# bbb_d300_cape.net
KiCad netlist of a schematic drawn in EAGLE
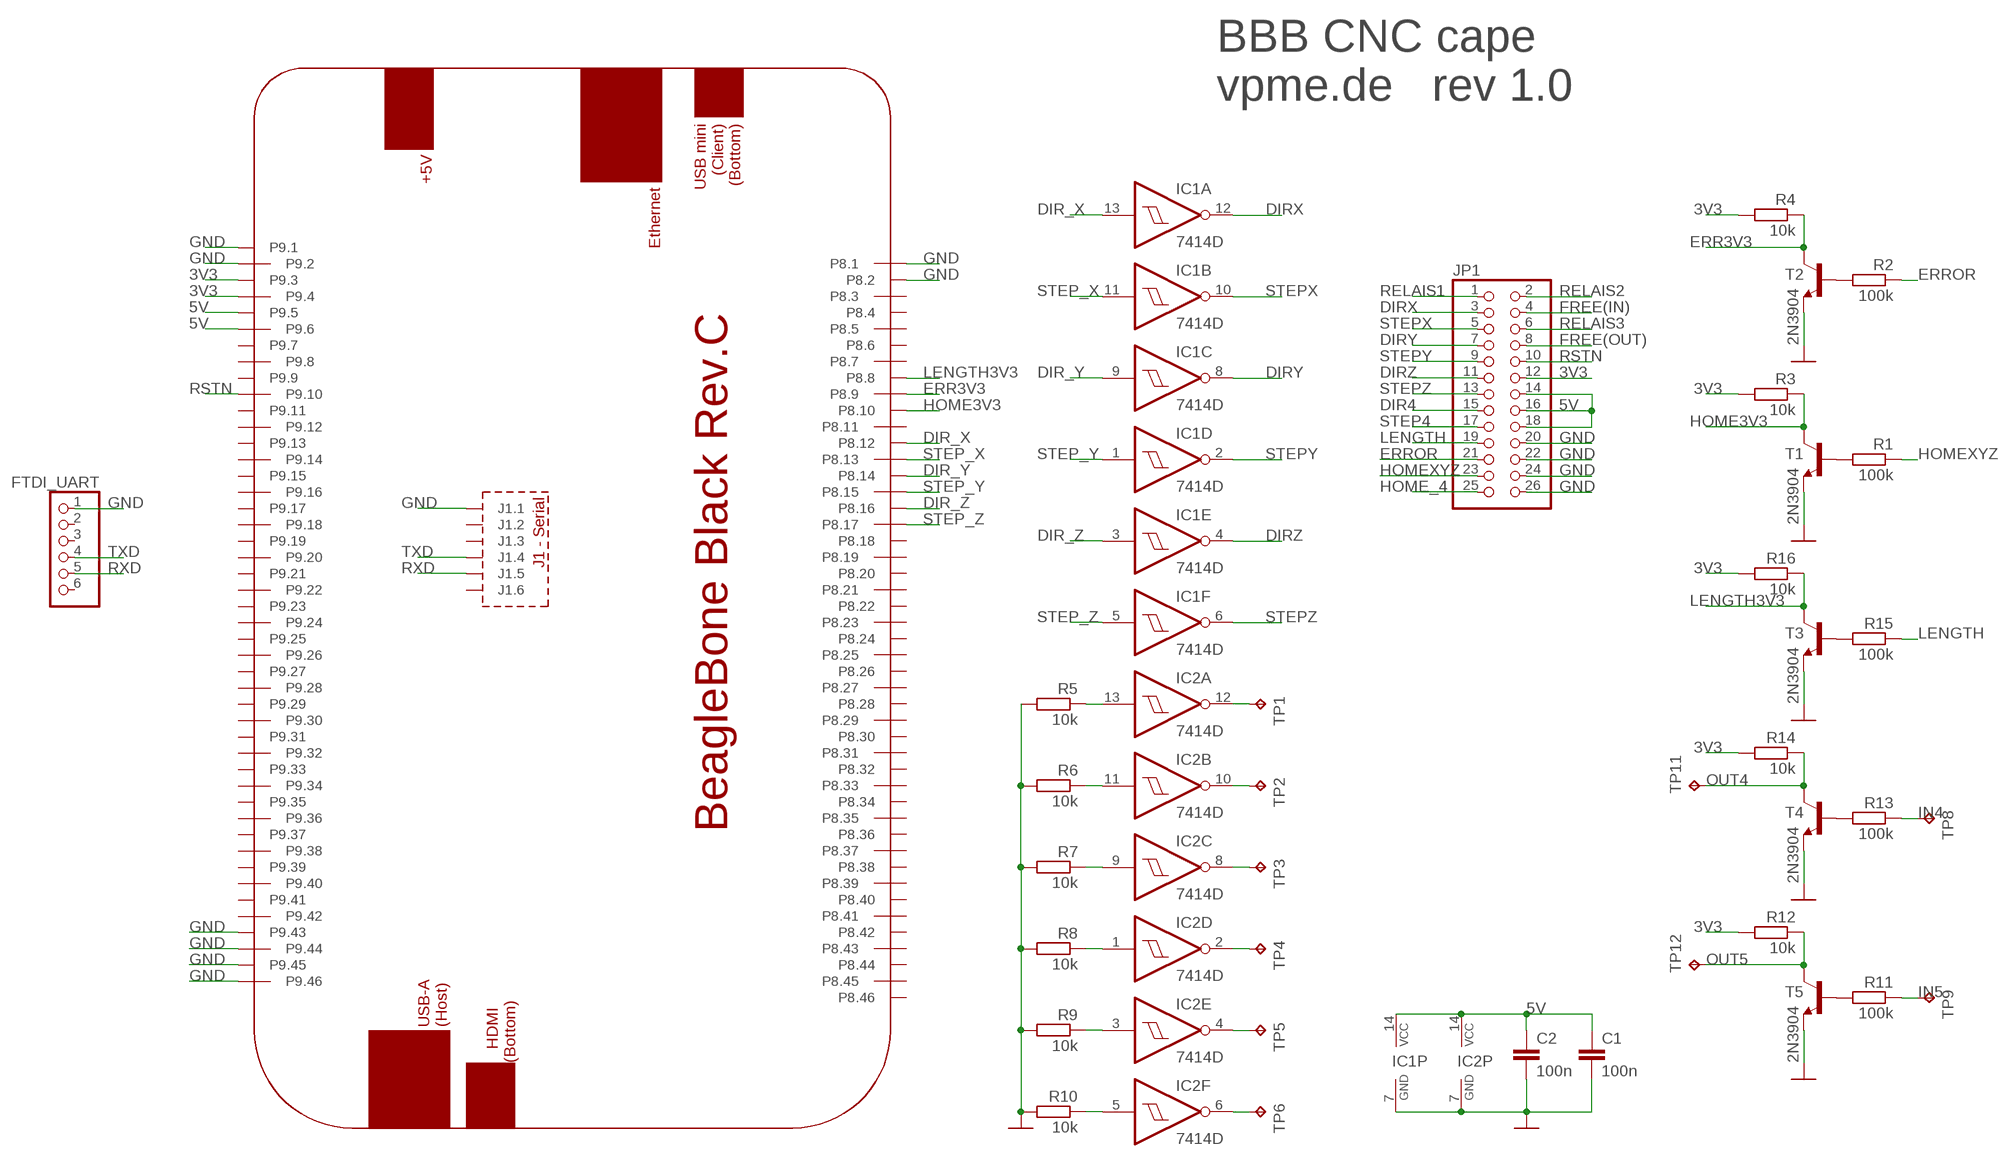
[diagram p0: schematic, sheet 1]

(export (version "E")
  (design (tool "Eeschema 10.0.6"))
  (components
    (comp (ref "C1")
      (value "100n")
      (footprint "eagle-import:C0603")
      (libsource (lib "eagle-import") (part "C-EUC0603"))
    )
    (comp (ref "C2")
      (value "100n")
      (footprint "eagle-import:C0603")
      (libsource (lib "eagle-import") (part "C-EUC0603"))
    )
    (comp (ref "FTDI_UART")
      (value "PINHD-1X6/90")
      (footprint "eagle-import:1X06_90")
      (libsource (lib "eagle-import") (part "PINHD-1X6/90"))
    )
    (comp (ref "IC1")
      (value "7414D")
      (footprint "eagle-import:SO14")
      (libsource (lib "eagle-import") (part "7414D"))
    )
    (comp (ref "IC2")
      (value "7414D")
      (footprint "eagle-import:SO14")
      (libsource (lib "eagle-import") (part "7414D"))
    )
    (comp (ref "JP1")
      (value "PINHD-2X13/90")
      (footprint "eagle-import:2X13_90")
      (libsource (lib "eagle-import") (part "PINHD-2X13/90"))
    )
    (comp (ref "PCB2")
      (value "BEAGLEBONE_BLACK_CAPE")
      (footprint "eagle-import:BEAGLEBONE_BLACK_CAPE")
      (libsource (lib "eagle-import") (part "BEAGLEBONE_BLACK_CAPE"))
    )
    (comp (ref "R1")
      (value "100k")
      (footprint "eagle-import:R0603")
      (libsource (lib "eagle-import") (part "R-EU_R0603"))
    )
    (comp (ref "R2")
      (value "100k")
      (footprint "eagle-import:R0603")
      (libsource (lib "eagle-import") (part "R-EU_R0603"))
    )
    (comp (ref "R3")
      (value "10k")
      (footprint "eagle-import:R0603")
      (libsource (lib "eagle-import") (part "R-EU_R0603"))
    )
    (comp (ref "R4")
      (value "10k")
      (footprint "eagle-import:R0603")
      (libsource (lib "eagle-import") (part "R-EU_R0603"))
    )
    (comp (ref "R5")
      (value "10k")
      (footprint "eagle-import:R0603")
      (libsource (lib "eagle-import") (part "R-EU_R0603"))
    )
    (comp (ref "R6")
      (value "10k")
      (footprint "eagle-import:R0603")
      (libsource (lib "eagle-import") (part "R-EU_R0603"))
    )
    (comp (ref "R7")
      (value "10k")
      (footprint "eagle-import:R0603")
      (libsource (lib "eagle-import") (part "R-EU_R0603"))
    )
    (comp (ref "R8")
      (value "10k")
      (footprint "eagle-import:R0603")
      (libsource (lib "eagle-import") (part "R-EU_R0603"))
    )
    (comp (ref "R9")
      (value "10k")
      (footprint "eagle-import:R0603")
      (libsource (lib "eagle-import") (part "R-EU_R0603"))
    )
    (comp (ref "R10")
      (value "10k")
      (footprint "eagle-import:R0603")
      (libsource (lib "eagle-import") (part "R-EU_R0603"))
    )
    (comp (ref "R11")
      (value "100k")
      (footprint "eagle-import:R0603")
      (libsource (lib "eagle-import") (part "R-EU_R0603"))
    )
    (comp (ref "R12")
      (value "10k")
      (footprint "eagle-import:R0603")
      (libsource (lib "eagle-import") (part "R-EU_R0603"))
    )
    (comp (ref "R13")
      (value "100k")
      (footprint "eagle-import:R0603")
      (libsource (lib "eagle-import") (part "R-EU_R0603"))
    )
    (comp (ref "R14")
      (value "10k")
      (footprint "eagle-import:R0603")
      (libsource (lib "eagle-import") (part "R-EU_R0603"))
    )
    (comp (ref "R15")
      (value "100k")
      (footprint "eagle-import:R0603")
      (libsource (lib "eagle-import") (part "R-EU_R0603"))
    )
    (comp (ref "R16")
      (value "10k")
      (footprint "eagle-import:R0603")
      (libsource (lib "eagle-import") (part "R-EU_R0603"))
    )
    (comp (ref "T1")
      (value "2N3904")
      (footprint "eagle-import:SOT23-BEC")
      (libsource (lib "eagle-import") (part "-NPN-SOT23-BECMMBT2222ALT1"))
    )
    (comp (ref "T2")
      (value "2N3904")
      (footprint "eagle-import:SOT23-BEC")
      (libsource (lib "eagle-import") (part "-NPN-SOT23-BECMMBT2222ALT1"))
    )
    (comp (ref "T3")
      (value "2N3904")
      (footprint "eagle-import:SOT23-BEC")
      (libsource (lib "eagle-import") (part "-NPN-SOT23-BECMMBT2222ALT1"))
    )
    (comp (ref "T4")
      (value "2N3904")
      (footprint "eagle-import:SOT23-BEC")
      (libsource (lib "eagle-import") (part "-NPN-SOT23-BECMMBT2222ALT1"))
    )
    (comp (ref "T5")
      (value "2N3904")
      (footprint "eagle-import:SOT23-BEC")
      (libsource (lib "eagle-import") (part "-NPN-SOT23-BECMMBT2222ALT1"))
    )
    (comp (ref "TP1")
      (value "TPTP12R")
      (footprint "eagle-import:TP12R")
      (libsource (lib "eagle-import") (part "TPTP12R"))
    )
    (comp (ref "TP2")
      (value "TPTP12R")
      (footprint "eagle-import:TP12R")
      (libsource (lib "eagle-import") (part "TPTP12R"))
    )
    (comp (ref "TP3")
      (value "TPTP12R")
      (footprint "eagle-import:TP12R")
      (libsource (lib "eagle-import") (part "TPTP12R"))
    )
    (comp (ref "TP4")
      (value "TPTP12R")
      (footprint "eagle-import:TP12R")
      (libsource (lib "eagle-import") (part "TPTP12R"))
    )
    (comp (ref "TP5")
      (value "TPTP12R")
      (footprint "eagle-import:TP12R")
      (libsource (lib "eagle-import") (part "TPTP12R"))
    )
    (comp (ref "TP6")
      (value "TPTP12R")
      (footprint "eagle-import:TP12R")
      (libsource (lib "eagle-import") (part "TPTP12R"))
    )
    (comp (ref "TP8")
      (value "TPTP12R")
      (footprint "eagle-import:TP12R")
      (libsource (lib "eagle-import") (part "TPTP12R"))
    )
    (comp (ref "TP9")
      (value "TPTP12R")
      (footprint "eagle-import:TP12R")
      (libsource (lib "eagle-import") (part "TPTP12R"))
    )
    (comp (ref "TP11")
      (value "TPTP12R")
      (footprint "eagle-import:TP12R")
      (libsource (lib "eagle-import") (part "TPTP12R"))
    )
    (comp (ref "TP12")
      (value "TPTP12R")
      (footprint "eagle-import:TP12R")
      (libsource (lib "eagle-import") (part "TPTP12R"))
    )
  )
  (nets
    (net (code "1") (name "/3V3") (class "Default")
      (node (ref "JP1") (pin "12") (pinfunction "12_12") (pintype "passive"))
      (node (ref "PCB2") (pin "P9.3") (pinfunction "P9.3_P9.3") (pintype "bidirectional"))
      (node (ref "PCB2") (pin "P9.4") (pinfunction "P9.4_P9.4") (pintype "bidirectional"))
      (node (ref "R12") (pin "2") (pinfunction "2_2") (pintype "passive"))
      (node (ref "R14") (pin "2") (pinfunction "2_2") (pintype "passive"))
      (node (ref "R16") (pin "2") (pinfunction "2_2") (pintype "passive"))
      (node (ref "R3") (pin "2") (pinfunction "2_2") (pintype "passive"))
      (node (ref "R4") (pin "2") (pinfunction "2_2") (pintype "passive"))
    )
    (net (code "2") (name "/5V") (class "Default")
      (node (ref "C1") (pin "1") (pinfunction "1_1") (pintype "passive"))
      (node (ref "C2") (pin "1") (pinfunction "1_1") (pintype "passive"))
      (node (ref "IC1") (pin "14") (pinfunction "VCC_14") (pintype "power_in"))
      (node (ref "IC2") (pin "14") (pinfunction "VCC_14") (pintype "power_in"))
      (node (ref "JP1") (pin "14") (pinfunction "14_14") (pintype "passive"))
      (node (ref "JP1") (pin "16") (pinfunction "16_16") (pintype "passive"))
      (node (ref "JP1") (pin "18") (pinfunction "18_18") (pintype "passive"))
      (node (ref "PCB2") (pin "P9.5") (pinfunction "P9.5_P9.5") (pintype "bidirectional"))
      (node (ref "PCB2") (pin "P9.6") (pinfunction "P9.6_P9.6") (pintype "bidirectional"))
    )
    (net (code "3") (name "/DIR4") (class "Default")
      (node (ref "JP1") (pin "15") (pinfunction "15_15") (pintype "passive"))
    )
    (net (code "4") (name "/DIRX") (class "Default")
      (node (ref "IC1") (pin "12") (pinfunction "O_12") (pintype "output"))
      (node (ref "JP1") (pin "3") (pinfunction "3_3") (pintype "passive"))
    )
    (net (code "5") (name "/DIRY") (class "Default")
      (node (ref "IC1") (pin "8") (pinfunction "O_8") (pintype "output"))
      (node (ref "JP1") (pin "7") (pinfunction "7_7") (pintype "passive"))
    )
    (net (code "6") (name "/DIRZ") (class "Default")
      (node (ref "IC1") (pin "4") (pinfunction "O_4") (pintype "output"))
      (node (ref "JP1") (pin "11") (pinfunction "11_11") (pintype "passive"))
    )
    (net (code "7") (name "/DIR_X") (class "Default")
      (node (ref "IC1") (pin "13") (pinfunction "I_13") (pintype "input"))
      (node (ref "PCB2") (pin "P8.12") (pinfunction "P8.12_P8.12") (pintype "bidirectional"))
    )
    (net (code "8") (name "/DIR_Y") (class "Default")
      (node (ref "IC1") (pin "9") (pinfunction "I_9") (pintype "input"))
      (node (ref "PCB2") (pin "P8.14") (pinfunction "P8.14_P8.14") (pintype "bidirectional"))
    )
    (net (code "9") (name "/DIR_Z") (class "Default")
      (node (ref "IC1") (pin "3") (pinfunction "I_3") (pintype "input"))
      (node (ref "PCB2") (pin "P8.16") (pinfunction "P8.16_P8.16") (pintype "bidirectional"))
    )
    (net (code "10") (name "/ERR3V3") (class "Default")
      (node (ref "PCB2") (pin "P8.9") (pinfunction "P8.9_P8.9") (pintype "bidirectional"))
      (node (ref "R4") (pin "1") (pinfunction "1_1") (pintype "passive"))
      (node (ref "T2") (pin "C") (pinfunction "C_C") (pintype "passive"))
    )
    (net (code "11") (name "/ERROR") (class "Default")
      (node (ref "JP1") (pin "21") (pinfunction "21_21") (pintype "passive"))
      (node (ref "R2") (pin "1") (pinfunction "1_1") (pintype "passive"))
    )
    (net (code "12") (name "/FREE(IN)") (class "Default")
      (node (ref "JP1") (pin "4") (pinfunction "4_4") (pintype "passive"))
    )
    (net (code "13") (name "/FREE(OUT)") (class "Default")
      (node (ref "JP1") (pin "8") (pinfunction "8_8") (pintype "passive"))
    )
    (net (code "14") (name "/HOME3V3") (class "Default")
      (node (ref "PCB2") (pin "P8.10") (pinfunction "P8.10_P8.10") (pintype "bidirectional"))
      (node (ref "R3") (pin "1") (pinfunction "1_1") (pintype "passive"))
      (node (ref "T1") (pin "C") (pinfunction "C_C") (pintype "passive"))
    )
    (net (code "15") (name "/HOMEXYZ") (class "Default")
      (node (ref "JP1") (pin "23") (pinfunction "23_23") (pintype "passive"))
      (node (ref "R1") (pin "1") (pinfunction "1_1") (pintype "passive"))
    )
    (net (code "16") (name "/HOME_4") (class "Default")
      (node (ref "JP1") (pin "25") (pinfunction "25_25") (pintype "passive"))
    )
    (net (code "17") (name "/IN4") (class "Default")
      (node (ref "R13") (pin "1") (pinfunction "1_1") (pintype "passive"))
      (node (ref "TP8") (pin "TP") (pinfunction "TP_TP") (pintype "input"))
    )
    (net (code "18") (name "/IN5") (class "Default")
      (node (ref "R11") (pin "1") (pinfunction "1_1") (pintype "passive"))
      (node (ref "TP9") (pin "TP") (pinfunction "TP_TP") (pintype "input"))
    )
    (net (code "19") (name "/LENGTH") (class "Default")
      (node (ref "JP1") (pin "19") (pinfunction "19_19") (pintype "passive"))
      (node (ref "R15") (pin "1") (pinfunction "1_1") (pintype "passive"))
    )
    (net (code "20") (name "/LENGTH3V3") (class "Default")
      (node (ref "PCB2") (pin "P8.8") (pinfunction "P8.8_P8.8") (pintype "bidirectional"))
      (node (ref "R16") (pin "1") (pinfunction "1_1") (pintype "passive"))
      (node (ref "T3") (pin "C") (pinfunction "C_C") (pintype "passive"))
    )
    (net (code "21") (name "/OUT4") (class "Default")
      (node (ref "R14") (pin "1") (pinfunction "1_1") (pintype "passive"))
      (node (ref "T4") (pin "C") (pinfunction "C_C") (pintype "passive"))
      (node (ref "TP11") (pin "TP") (pinfunction "TP_TP") (pintype "input"))
    )
    (net (code "22") (name "/OUT5") (class "Default")
      (node (ref "R12") (pin "1") (pinfunction "1_1") (pintype "passive"))
      (node (ref "T5") (pin "C") (pinfunction "C_C") (pintype "passive"))
      (node (ref "TP12") (pin "TP") (pinfunction "TP_TP") (pintype "input"))
    )
    (net (code "23") (name "/RELAIS1") (class "Default")
      (node (ref "JP1") (pin "1") (pinfunction "1_1") (pintype "passive"))
    )
    (net (code "24") (name "/RELAIS2") (class "Default")
      (node (ref "JP1") (pin "2") (pinfunction "2_2") (pintype "passive"))
    )
    (net (code "25") (name "/RELAIS3") (class "Default")
      (node (ref "JP1") (pin "6") (pinfunction "6_6") (pintype "passive"))
    )
    (net (code "26") (name "/RSTN") (class "Default")
      (node (ref "JP1") (pin "10") (pinfunction "10_10") (pintype "passive"))
      (node (ref "PCB2") (pin "P9.10") (pinfunction "P9.10_P9.10") (pintype "bidirectional"))
    )
    (net (code "27") (name "/RXD") (class "Default")
      (node (ref "FTDI_UART") (pin "5") (pinfunction "5_5") (pintype "passive"))
      (node (ref "PCB2") (pin "J1.5") (pinfunction "J1.5_J1.5") (pintype "bidirectional"))
    )
    (net (code "28") (name "/STEP4") (class "Default")
      (node (ref "JP1") (pin "17") (pinfunction "17_17") (pintype "passive"))
    )
    (net (code "29") (name "/STEPX") (class "Default")
      (node (ref "IC1") (pin "10") (pinfunction "O_10") (pintype "output"))
      (node (ref "JP1") (pin "5") (pinfunction "5_5") (pintype "passive"))
    )
    (net (code "30") (name "/STEPY") (class "Default")
      (node (ref "IC1") (pin "2") (pinfunction "O_2") (pintype "output"))
      (node (ref "JP1") (pin "9") (pinfunction "9_9") (pintype "passive"))
    )
    (net (code "31") (name "/STEPZ") (class "Default")
      (node (ref "IC1") (pin "6") (pinfunction "O_6") (pintype "output"))
      (node (ref "JP1") (pin "13") (pinfunction "13_13") (pintype "passive"))
    )
    (net (code "32") (name "/STEP_X") (class "Default")
      (node (ref "IC1") (pin "11") (pinfunction "I_11") (pintype "input"))
      (node (ref "PCB2") (pin "P8.13") (pinfunction "P8.13_P8.13") (pintype "bidirectional"))
    )
    (net (code "33") (name "/STEP_Y") (class "Default")
      (node (ref "IC1") (pin "1") (pinfunction "I_1") (pintype "input"))
      (node (ref "PCB2") (pin "P8.15") (pinfunction "P8.15_P8.15") (pintype "bidirectional"))
    )
    (net (code "34") (name "/STEP_Z") (class "Default")
      (node (ref "IC1") (pin "5") (pinfunction "I_5") (pintype "input"))
      (node (ref "PCB2") (pin "P8.17") (pinfunction "P8.17_P8.17") (pintype "bidirectional"))
    )
    (net (code "35") (name "/TXD") (class "Default")
      (node (ref "FTDI_UART") (pin "4") (pinfunction "4_4") (pintype "passive"))
      (node (ref "PCB2") (pin "J1.4") (pinfunction "J1.4_J1.4") (pintype "bidirectional"))
    )
    (net (code "36") (name "GND") (class "Default")
      (node (ref "C1") (pin "2") (pinfunction "2_2") (pintype "passive"))
      (node (ref "C2") (pin "2") (pinfunction "2_2") (pintype "passive"))
      (node (ref "FTDI_UART") (pin "1") (pinfunction "1_1") (pintype "passive"))
      (node (ref "IC1") (pin "7") (pinfunction "GND_7") (pintype "power_in"))
      (node (ref "IC2") (pin "7") (pinfunction "GND_7") (pintype "power_in"))
      (node (ref "JP1") (pin "20") (pinfunction "20_20") (pintype "passive"))
      (node (ref "JP1") (pin "22") (pinfunction "22_22") (pintype "passive"))
      (node (ref "JP1") (pin "24") (pinfunction "24_24") (pintype "passive"))
      (node (ref "JP1") (pin "26") (pinfunction "26_26") (pintype "passive"))
      (node (ref "PCB2") (pin "J1.1") (pinfunction "J1.1_J1.1") (pintype "bidirectional"))
      (node (ref "PCB2") (pin "P8.1") (pinfunction "P8.1_P8.1") (pintype "bidirectional"))
      (node (ref "PCB2") (pin "P8.2") (pinfunction "P8.2_P8.2") (pintype "bidirectional"))
      (node (ref "PCB2") (pin "P9.1") (pinfunction "P9.1_P9.1") (pintype "bidirectional"))
      (node (ref "PCB2") (pin "P9.2") (pinfunction "P9.2_P9.2") (pintype "bidirectional"))
      (node (ref "PCB2") (pin "P9.43") (pinfunction "P9.43_P9.43") (pintype "bidirectional"))
      (node (ref "PCB2") (pin "P9.44") (pinfunction "P9.44_P9.44") (pintype "bidirectional"))
      (node (ref "PCB2") (pin "P9.45") (pinfunction "P9.45_P9.45") (pintype "bidirectional"))
      (node (ref "PCB2") (pin "P9.46") (pinfunction "P9.46_P9.46") (pintype "bidirectional"))
      (node (ref "R10") (pin "2") (pinfunction "2_2") (pintype "passive"))
      (node (ref "R5") (pin "2") (pinfunction "2_2") (pintype "passive"))
      (node (ref "R6") (pin "2") (pinfunction "2_2") (pintype "passive"))
      (node (ref "R7") (pin "2") (pinfunction "2_2") (pintype "passive"))
      (node (ref "R8") (pin "2") (pinfunction "2_2") (pintype "passive"))
      (node (ref "R9") (pin "2") (pinfunction "2_2") (pintype "passive"))
      (node (ref "T1") (pin "E") (pinfunction "E_E") (pintype "passive"))
      (node (ref "T2") (pin "E") (pinfunction "E_E") (pintype "passive"))
      (node (ref "T3") (pin "E") (pinfunction "E_E") (pintype "passive"))
      (node (ref "T4") (pin "E") (pinfunction "E_E") (pintype "passive"))
      (node (ref "T5") (pin "E") (pinfunction "E_E") (pintype "passive"))
    )
    (net (code "37") (name "Net-(IC2A-I)") (class "Default")
      (node (ref "IC2") (pin "13") (pinfunction "I_13") (pintype "input"))
      (node (ref "R5") (pin "1") (pinfunction "1_1") (pintype "passive"))
    )
    (net (code "38") (name "Net-(IC2A-O)") (class "Default")
      (node (ref "IC2") (pin "12") (pinfunction "O_12") (pintype "output"))
      (node (ref "TP1") (pin "TP") (pinfunction "TP_TP") (pintype "input"))
    )
    (net (code "39") (name "Net-(IC2B-I)") (class "Default")
      (node (ref "IC2") (pin "11") (pinfunction "I_11") (pintype "input"))
      (node (ref "R6") (pin "1") (pinfunction "1_1") (pintype "passive"))
    )
    (net (code "40") (name "Net-(IC2B-O)") (class "Default")
      (node (ref "IC2") (pin "10") (pinfunction "O_10") (pintype "output"))
      (node (ref "TP2") (pin "TP") (pinfunction "TP_TP") (pintype "input"))
    )
    (net (code "41") (name "Net-(IC2C-I)") (class "Default")
      (node (ref "IC2") (pin "9") (pinfunction "I_9") (pintype "input"))
      (node (ref "R7") (pin "1") (pinfunction "1_1") (pintype "passive"))
    )
    (net (code "42") (name "Net-(IC2C-O)") (class "Default")
      (node (ref "IC2") (pin "8") (pinfunction "O_8") (pintype "output"))
      (node (ref "TP3") (pin "TP") (pinfunction "TP_TP") (pintype "input"))
    )
    (net (code "43") (name "Net-(IC2D-I)") (class "Default")
      (node (ref "IC2") (pin "1") (pinfunction "I_1") (pintype "input"))
      (node (ref "R8") (pin "1") (pinfunction "1_1") (pintype "passive"))
    )
    (net (code "44") (name "Net-(IC2D-O)") (class "Default")
      (node (ref "IC2") (pin "2") (pinfunction "O_2") (pintype "output"))
      (node (ref "TP4") (pin "TP") (pinfunction "TP_TP") (pintype "input"))
    )
    (net (code "45") (name "Net-(IC2E-I)") (class "Default")
      (node (ref "IC2") (pin "3") (pinfunction "I_3") (pintype "input"))
      (node (ref "R9") (pin "1") (pinfunction "1_1") (pintype "passive"))
    )
    (net (code "46") (name "Net-(IC2E-O)") (class "Default")
      (node (ref "IC2") (pin "4") (pinfunction "O_4") (pintype "output"))
      (node (ref "TP5") (pin "TP") (pinfunction "TP_TP") (pintype "input"))
    )
    (net (code "47") (name "Net-(IC2F-I)") (class "Default")
      (node (ref "IC2") (pin "5") (pinfunction "I_5") (pintype "input"))
      (node (ref "R10") (pin "1") (pinfunction "1_1") (pintype "passive"))
    )
    (net (code "48") (name "Net-(IC2F-O)") (class "Default")
      (node (ref "IC2") (pin "6") (pinfunction "O_6") (pintype "output"))
      (node (ref "TP6") (pin "TP") (pinfunction "TP_TP") (pintype "input"))
    )
    (net (code "49") (name "Net-(R1-Pad2)") (class "Default")
      (node (ref "R1") (pin "2") (pinfunction "2_2") (pintype "passive"))
      (node (ref "T1") (pin "B") (pinfunction "B_B") (pintype "passive"))
    )
    (net (code "50") (name "Net-(R2-Pad2)") (class "Default")
      (node (ref "R2") (pin "2") (pinfunction "2_2") (pintype "passive"))
      (node (ref "T2") (pin "B") (pinfunction "B_B") (pintype "passive"))
    )
    (net (code "51") (name "Net-(R11-Pad2)") (class "Default")
      (node (ref "R11") (pin "2") (pinfunction "2_2") (pintype "passive"))
      (node (ref "T5") (pin "B") (pinfunction "B_B") (pintype "passive"))
    )
    (net (code "52") (name "Net-(R13-Pad2)") (class "Default")
      (node (ref "R13") (pin "2") (pinfunction "2_2") (pintype "passive"))
      (node (ref "T4") (pin "B") (pinfunction "B_B") (pintype "passive"))
    )
    (net (code "53") (name "Net-(R15-Pad2)") (class "Default")
      (node (ref "R15") (pin "2") (pinfunction "2_2") (pintype "passive"))
      (node (ref "T3") (pin "B") (pinfunction "B_B") (pintype "passive"))
    )
    (net (code "54") (name "unconnected-(FTDI_UART-Pad2)") (class "Default")
      (node (ref "FTDI_UART") (pin "2") (pinfunction "2_2") (pintype "passive"))
    )
    (net (code "55") (name "unconnected-(FTDI_UART-Pad3)") (class "Default")
      (node (ref "FTDI_UART") (pin "3") (pinfunction "3_3") (pintype "passive"))
    )
    (net (code "56") (name "unconnected-(FTDI_UART-Pad6)") (class "Default")
      (node (ref "FTDI_UART") (pin "6") (pinfunction "6_6") (pintype "passive"))
    )
    (net (code "57") (name "unconnected-(PCB2-PadJ1.2)") (class "Default")
      (node (ref "PCB2") (pin "J1.2") (pinfunction "J1.2_J1.2") (pintype "bidirectional"))
    )
    (net (code "58") (name "unconnected-(PCB2-PadJ1.3)") (class "Default")
      (node (ref "PCB2") (pin "J1.3") (pinfunction "J1.3_J1.3") (pintype "bidirectional"))
    )
    (net (code "59") (name "unconnected-(PCB2-PadJ1.6)") (class "Default")
      (node (ref "PCB2") (pin "J1.6") (pinfunction "J1.6_J1.6") (pintype "bidirectional"))
    )
    (net (code "60") (name "unconnected-(PCB2-PadP8.3)") (class "Default")
      (node (ref "PCB2") (pin "P8.3") (pinfunction "P8.3_P8.3") (pintype "bidirectional"))
    )
    (net (code "61") (name "unconnected-(PCB2-PadP8.4)") (class "Default")
      (node (ref "PCB2") (pin "P8.4") (pinfunction "P8.4_P8.4") (pintype "bidirectional"))
    )
    (net (code "62") (name "unconnected-(PCB2-PadP8.5)") (class "Default")
      (node (ref "PCB2") (pin "P8.5") (pinfunction "P8.5_P8.5") (pintype "bidirectional"))
    )
    (net (code "63") (name "unconnected-(PCB2-PadP8.6)") (class "Default")
      (node (ref "PCB2") (pin "P8.6") (pinfunction "P8.6_P8.6") (pintype "bidirectional"))
    )
    (net (code "64") (name "unconnected-(PCB2-PadP8.7)") (class "Default")
      (node (ref "PCB2") (pin "P8.7") (pinfunction "P8.7_P8.7") (pintype "bidirectional"))
    )
    (net (code "65") (name "unconnected-(PCB2-PadP8.11)") (class "Default")
      (node (ref "PCB2") (pin "P8.11") (pinfunction "P8.11_P8.11") (pintype "bidirectional"))
    )
    (net (code "66") (name "unconnected-(PCB2-PadP8.18)") (class "Default")
      (node (ref "PCB2") (pin "P8.18") (pinfunction "P8.18_P8.18") (pintype "bidirectional"))
    )
    (net (code "67") (name "unconnected-(PCB2-PadP8.19)") (class "Default")
      (node (ref "PCB2") (pin "P8.19") (pinfunction "P8.19_P8.19") (pintype "bidirectional"))
    )
    (net (code "68") (name "unconnected-(PCB2-PadP8.20)") (class "Default")
      (node (ref "PCB2") (pin "P8.20") (pinfunction "P8.20_P8.20") (pintype "bidirectional"))
    )
    (net (code "69") (name "unconnected-(PCB2-PadP8.21)") (class "Default")
      (node (ref "PCB2") (pin "P8.21") (pinfunction "P8.21_P8.21") (pintype "bidirectional"))
    )
    (net (code "70") (name "unconnected-(PCB2-PadP8.22)") (class "Default")
      (node (ref "PCB2") (pin "P8.22") (pinfunction "P8.22_P8.22") (pintype "bidirectional"))
    )
    (net (code "71") (name "unconnected-(PCB2-PadP8.23)") (class "Default")
      (node (ref "PCB2") (pin "P8.23") (pinfunction "P8.23_P8.23") (pintype "bidirectional"))
    )
    (net (code "72") (name "unconnected-(PCB2-PadP8.24)") (class "Default")
      (node (ref "PCB2") (pin "P8.24") (pinfunction "P8.24_P8.24") (pintype "bidirectional"))
    )
    (net (code "73") (name "unconnected-(PCB2-PadP8.25)") (class "Default")
      (node (ref "PCB2") (pin "P8.25") (pinfunction "P8.25_P8.25") (pintype "bidirectional"))
    )
    (net (code "74") (name "unconnected-(PCB2-PadP8.26)") (class "Default")
      (node (ref "PCB2") (pin "P8.26") (pinfunction "P8.26_P8.26") (pintype "bidirectional"))
    )
    (net (code "75") (name "unconnected-(PCB2-PadP8.27)") (class "Default")
      (node (ref "PCB2") (pin "P8.27") (pinfunction "P8.27_P8.27") (pintype "bidirectional"))
    )
    (net (code "76") (name "unconnected-(PCB2-PadP8.28)") (class "Default")
      (node (ref "PCB2") (pin "P8.28") (pinfunction "P8.28_P8.28") (pintype "bidirectional"))
    )
    (net (code "77") (name "unconnected-(PCB2-PadP8.29)") (class "Default")
      (node (ref "PCB2") (pin "P8.29") (pinfunction "P8.29_P8.29") (pintype "bidirectional"))
    )
    (net (code "78") (name "unconnected-(PCB2-PadP8.30)") (class "Default")
      (node (ref "PCB2") (pin "P8.30") (pinfunction "P8.30_P8.30") (pintype "bidirectional"))
    )
    (net (code "79") (name "unconnected-(PCB2-PadP8.31)") (class "Default")
      (node (ref "PCB2") (pin "P8.31") (pinfunction "P8.31_P8.31") (pintype "bidirectional"))
    )
    (net (code "80") (name "unconnected-(PCB2-PadP8.32)") (class "Default")
      (node (ref "PCB2") (pin "P8.32") (pinfunction "P8.32_P8.32") (pintype "bidirectional"))
    )
    (net (code "81") (name "unconnected-(PCB2-PadP8.33)") (class "Default")
      (node (ref "PCB2") (pin "P8.33") (pinfunction "P8.33_P8.33") (pintype "bidirectional"))
    )
    (net (code "82") (name "unconnected-(PCB2-PadP8.34)") (class "Default")
      (node (ref "PCB2") (pin "P8.34") (pinfunction "P8.34_P8.34") (pintype "bidirectional"))
    )
    (net (code "83") (name "unconnected-(PCB2-PadP8.35)") (class "Default")
      (node (ref "PCB2") (pin "P8.35") (pinfunction "P8.35_P8.35") (pintype "bidirectional"))
    )
    (net (code "84") (name "unconnected-(PCB2-PadP8.36)") (class "Default")
      (node (ref "PCB2") (pin "P8.36") (pinfunction "P8.36_P8.36") (pintype "bidirectional"))
    )
    (net (code "85") (name "unconnected-(PCB2-PadP8.37)") (class "Default")
      (node (ref "PCB2") (pin "P8.37") (pinfunction "P8.37_P8.37") (pintype "bidirectional"))
    )
    (net (code "86") (name "unconnected-(PCB2-PadP8.38)") (class "Default")
      (node (ref "PCB2") (pin "P8.38") (pinfunction "P8.38_P8.38") (pintype "bidirectional"))
    )
    (net (code "87") (name "unconnected-(PCB2-PadP8.39)") (class "Default")
      (node (ref "PCB2") (pin "P8.39") (pinfunction "P8.39_P8.39") (pintype "bidirectional"))
    )
    (net (code "88") (name "unconnected-(PCB2-PadP8.40)") (class "Default")
      (node (ref "PCB2") (pin "P8.40") (pinfunction "P8.40_P8.40") (pintype "bidirectional"))
    )
    (net (code "89") (name "unconnected-(PCB2-PadP8.41)") (class "Default")
      (node (ref "PCB2") (pin "P8.41") (pinfunction "P8.41_P8.41") (pintype "bidirectional"))
    )
    (net (code "90") (name "unconnected-(PCB2-PadP8.42)") (class "Default")
      (node (ref "PCB2") (pin "P8.42") (pinfunction "P8.42_P8.42") (pintype "bidirectional"))
    )
    (net (code "91") (name "unconnected-(PCB2-PadP8.43)") (class "Default")
      (node (ref "PCB2") (pin "P8.43") (pinfunction "P8.43_P8.43") (pintype "bidirectional"))
    )
    (net (code "92") (name "unconnected-(PCB2-PadP8.44)") (class "Default")
      (node (ref "PCB2") (pin "P8.44") (pinfunction "P8.44_P8.44") (pintype "bidirectional"))
    )
    (net (code "93") (name "unconnected-(PCB2-PadP8.45)") (class "Default")
      (node (ref "PCB2") (pin "P8.45") (pinfunction "P8.45_P8.45") (pintype "bidirectional"))
    )
    (net (code "94") (name "unconnected-(PCB2-PadP8.46)") (class "Default")
      (node (ref "PCB2") (pin "P8.46") (pinfunction "P8.46_P8.46") (pintype "bidirectional"))
    )
    (net (code "95") (name "unconnected-(PCB2-PadP9.7)") (class "Default")
      (node (ref "PCB2") (pin "P9.7") (pinfunction "P9.7_P9.7") (pintype "bidirectional"))
    )
    (net (code "96") (name "unconnected-(PCB2-PadP9.8)") (class "Default")
      (node (ref "PCB2") (pin "P9.8") (pinfunction "P9.8_P9.8") (pintype "bidirectional"))
    )
    (net (code "97") (name "unconnected-(PCB2-PadP9.9)") (class "Default")
      (node (ref "PCB2") (pin "P9.9") (pinfunction "P9.9_P9.9") (pintype "bidirectional"))
    )
    (net (code "98") (name "unconnected-(PCB2-PadP9.11)") (class "Default")
      (node (ref "PCB2") (pin "P9.11") (pinfunction "P9.11_P9.11") (pintype "bidirectional"))
    )
    (net (code "99") (name "unconnected-(PCB2-PadP9.12)") (class "Default")
      (node (ref "PCB2") (pin "P9.12") (pinfunction "P9.12_P9.12") (pintype "bidirectional"))
    )
    (net (code "100") (name "unconnected-(PCB2-PadP9.13)") (class "Default")
      (node (ref "PCB2") (pin "P9.13") (pinfunction "P9.13_P9.13") (pintype "bidirectional"))
    )
    (net (code "101") (name "unconnected-(PCB2-PadP9.14)") (class "Default")
      (node (ref "PCB2") (pin "P9.14") (pinfunction "P9.14_P9.14") (pintype "bidirectional"))
    )
    (net (code "102") (name "unconnected-(PCB2-PadP9.15)") (class "Default")
      (node (ref "PCB2") (pin "P9.15") (pinfunction "P9.15_P9.15") (pintype "bidirectional"))
    )
    (net (code "103") (name "unconnected-(PCB2-PadP9.16)") (class "Default")
      (node (ref "PCB2") (pin "P9.16") (pinfunction "P9.16_P9.16") (pintype "bidirectional"))
    )
    (net (code "104") (name "unconnected-(PCB2-PadP9.17)") (class "Default")
      (node (ref "PCB2") (pin "P9.17") (pinfunction "P9.17_P9.17") (pintype "bidirectional"))
    )
    (net (code "105") (name "unconnected-(PCB2-PadP9.18)") (class "Default")
      (node (ref "PCB2") (pin "P9.18") (pinfunction "P9.18_P9.18") (pintype "bidirectional"))
    )
    (net (code "106") (name "unconnected-(PCB2-PadP9.19)") (class "Default")
      (node (ref "PCB2") (pin "P9.19") (pinfunction "P9.19_P9.19") (pintype "bidirectional"))
    )
    (net (code "107") (name "unconnected-(PCB2-PadP9.20)") (class "Default")
      (node (ref "PCB2") (pin "P9.20") (pinfunction "P9.20_P9.20") (pintype "bidirectional"))
    )
    (net (code "108") (name "unconnected-(PCB2-PadP9.21)") (class "Default")
      (node (ref "PCB2") (pin "P9.21") (pinfunction "P9.21_P9.21") (pintype "bidirectional"))
    )
    (net (code "109") (name "unconnected-(PCB2-PadP9.22)") (class "Default")
      (node (ref "PCB2") (pin "P9.22") (pinfunction "P9.22_P9.22") (pintype "bidirectional"))
    )
    (net (code "110") (name "unconnected-(PCB2-PadP9.23)") (class "Default")
      (node (ref "PCB2") (pin "P9.23") (pinfunction "P9.23_P9.23") (pintype "bidirectional"))
    )
    (net (code "111") (name "unconnected-(PCB2-PadP9.24)") (class "Default")
      (node (ref "PCB2") (pin "P9.24") (pinfunction "P9.24_P9.24") (pintype "bidirectional"))
    )
    (net (code "112") (name "unconnected-(PCB2-PadP9.25)") (class "Default")
      (node (ref "PCB2") (pin "P9.25") (pinfunction "P9.25_P9.25") (pintype "bidirectional"))
    )
    (net (code "113") (name "unconnected-(PCB2-PadP9.26)") (class "Default")
      (node (ref "PCB2") (pin "P9.26") (pinfunction "P9.26_P9.26") (pintype "bidirectional"))
    )
    (net (code "114") (name "unconnected-(PCB2-PadP9.27)") (class "Default")
      (node (ref "PCB2") (pin "P9.27") (pinfunction "P9.27_P9.27") (pintype "bidirectional"))
    )
    (net (code "115") (name "unconnected-(PCB2-PadP9.28)") (class "Default")
      (node (ref "PCB2") (pin "P9.28") (pinfunction "P9.28_P9.28") (pintype "bidirectional"))
    )
    (net (code "116") (name "unconnected-(PCB2-PadP9.29)") (class "Default")
      (node (ref "PCB2") (pin "P9.29") (pinfunction "P9.29_P9.29") (pintype "bidirectional"))
    )
    (net (code "117") (name "unconnected-(PCB2-PadP9.30)") (class "Default")
      (node (ref "PCB2") (pin "P9.30") (pinfunction "P9.30_P9.30") (pintype "bidirectional"))
    )
    (net (code "118") (name "unconnected-(PCB2-PadP9.31)") (class "Default")
      (node (ref "PCB2") (pin "P9.31") (pinfunction "P9.31_P9.31") (pintype "bidirectional"))
    )
    (net (code "119") (name "unconnected-(PCB2-PadP9.32)") (class "Default")
      (node (ref "PCB2") (pin "P9.32") (pinfunction "P9.32_P9.32") (pintype "bidirectional"))
    )
    (net (code "120") (name "unconnected-(PCB2-PadP9.33)") (class "Default")
      (node (ref "PCB2") (pin "P9.33") (pinfunction "P9.33_P9.33") (pintype "bidirectional"))
    )
    (net (code "121") (name "unconnected-(PCB2-PadP9.34)") (class "Default")
      (node (ref "PCB2") (pin "P9.34") (pinfunction "P9.34_P9.34") (pintype "bidirectional"))
    )
    (net (code "122") (name "unconnected-(PCB2-PadP9.35)") (class "Default")
      (node (ref "PCB2") (pin "P9.35") (pinfunction "P9.35_P9.35") (pintype "bidirectional"))
    )
    (net (code "123") (name "unconnected-(PCB2-PadP9.36)") (class "Default")
      (node (ref "PCB2") (pin "P9.36") (pinfunction "P9.36_P9.36") (pintype "bidirectional"))
    )
    (net (code "124") (name "unconnected-(PCB2-PadP9.37)") (class "Default")
      (node (ref "PCB2") (pin "P9.37") (pinfunction "P9.37_P9.37") (pintype "bidirectional"))
    )
    (net (code "125") (name "unconnected-(PCB2-PadP9.38)") (class "Default")
      (node (ref "PCB2") (pin "P9.38") (pinfunction "P9.38_P9.38") (pintype "bidirectional"))
    )
    (net (code "126") (name "unconnected-(PCB2-PadP9.39)") (class "Default")
      (node (ref "PCB2") (pin "P9.39") (pinfunction "P9.39_P9.39") (pintype "bidirectional"))
    )
    (net (code "127") (name "unconnected-(PCB2-PadP9.40)") (class "Default")
      (node (ref "PCB2") (pin "P9.40") (pinfunction "P9.40_P9.40") (pintype "bidirectional"))
    )
    (net (code "128") (name "unconnected-(PCB2-PadP9.41)") (class "Default")
      (node (ref "PCB2") (pin "P9.41") (pinfunction "P9.41_P9.41") (pintype "bidirectional"))
    )
    (net (code "129") (name "unconnected-(PCB2-PadP9.42)") (class "Default")
      (node (ref "PCB2") (pin "P9.42") (pinfunction "P9.42_P9.42") (pintype "bidirectional"))
    )
  )
)
